# SCH_Project_Final.net
KiCad netlist of a schematic drawn in Altium Designer
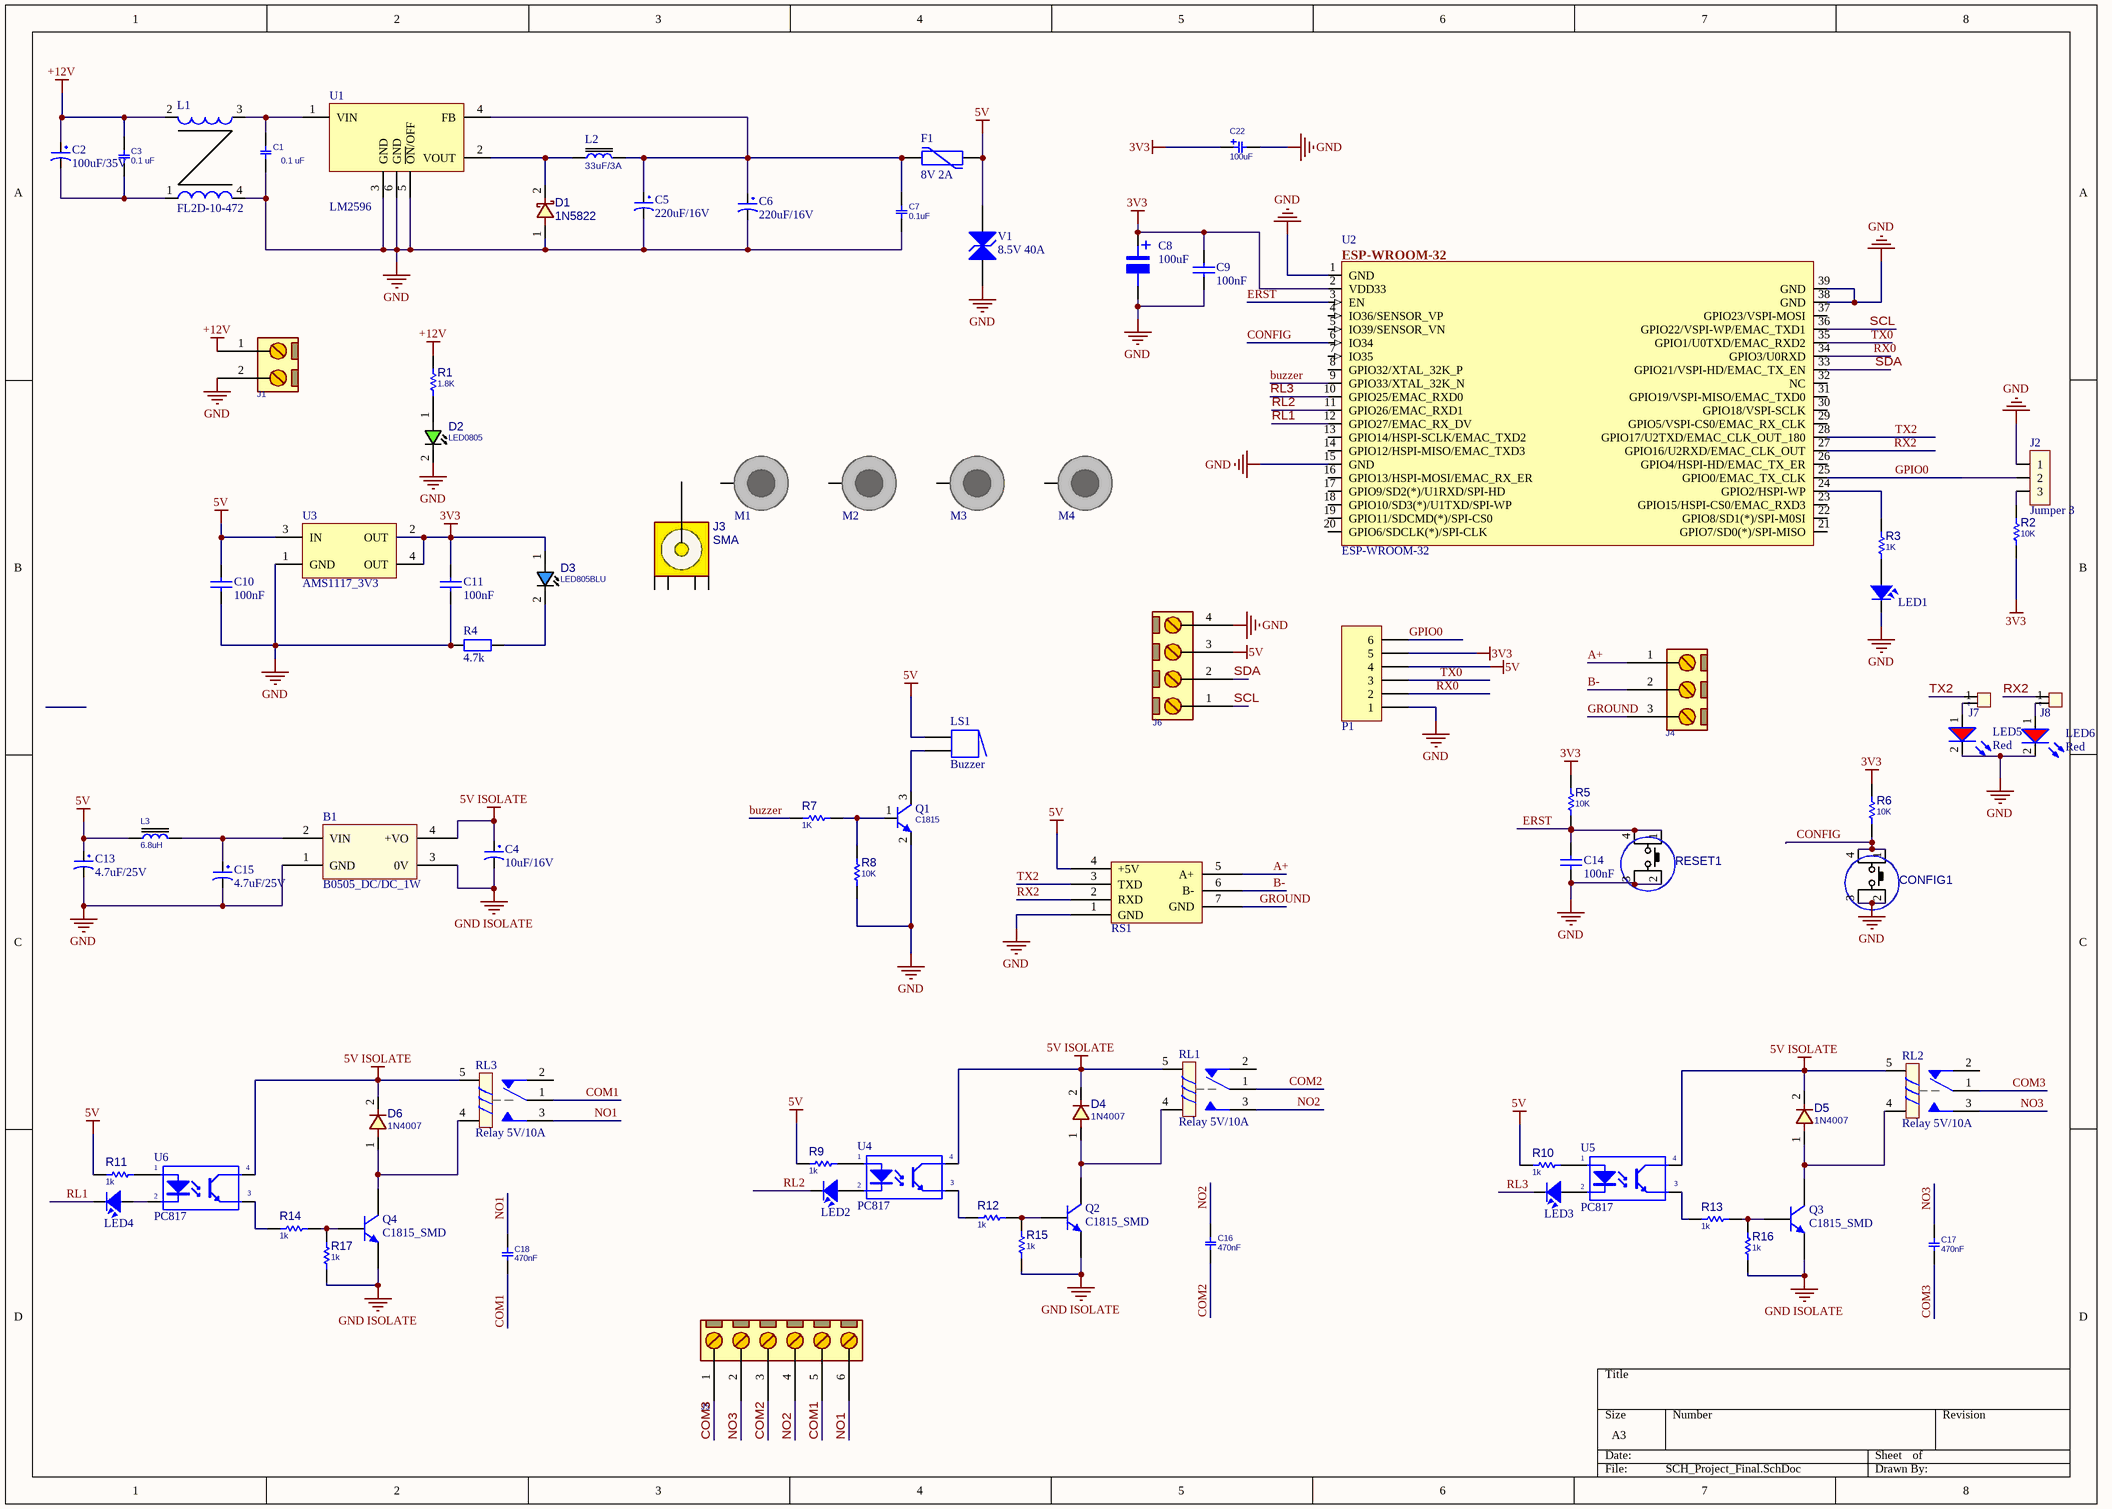
[diagram p0: SCH_Project_Final.SchDoc]

(export (version "E")
  (design (tool "Eeschema 10.0.6"))
  (components
    (comp (ref "B1")
      (value "B0505_DC/DC_1W")
      (footprint "B0505S_DC/DC_1W")
      (libsource (lib "TRANTHANHSANG") (part "B0505_DC/DC_1W"))
    )
    (comp (ref "C1")
      (value "0.1 uF")
      (footprint "cap_0805")
      (description "CAP, MLCC, -F, -V, MATERIAL, -%, 0201")
      (fields (field (name "MANF_P#") "MANF_PART#"))
      (libsource (lib "TRANTHANHSANG") (part "CAP_SMD_0805"))
    )
    (comp (ref "C2")
      (value "100uF/35V")
      (footprint "tu hoa 6.5mm")
      (description "Cắm")
      (libsource (lib "THU VIEN SCH") (part "Tu Hoa 47uF 50V 6x11"))
    )
    (comp (ref "C3")
      (value "0.1 uF")
      (footprint "cap_0805")
      (description "CAP, MLCC, -F, -V, MATERIAL, -%, 0201")
      (fields (field (name "MANF_P#") "MANF_PART#"))
      (libsource (lib "TRANTHANHSANG") (part "CAP_SMD_0805"))
    )
    (comp (ref "C4")
      (value "10uF/16V")
      (footprint "tu hoa 5mm")
      (description "Cắm")
      (libsource (lib "THU VIEN SCH") (part "Tu Hoa 100uF 16V 5x7"))
    )
    (comp (ref "C5")
      (value "220uF/16V")
      (footprint "tu hoa 6.5mm")
      (description "Cắm")
      (libsource (lib "THU VIEN SCH") (part "Tu Hoa 100uF 35V 6x8"))
    )
    (comp (ref "C6")
      (value "220uF/16V")
      (footprint "tu hoa 6.5mm")
      (description "Cắm")
      (libsource (lib "THU VIEN SCH") (part "Tu Hoa 100uF 35V 6x8"))
    )
    (comp (ref "C7")
      (value "0.1uF")
      (footprint "cap_0805")
      (description "CAP, MLCC, -F, -V, MATERIAL, -%, 0201")
      (fields (field (name "MANF_P#") "MANF_PART#"))
      (libsource (lib "TRANTHANHSANG") (part "CAP_SMD_0805"))
    )
    (comp (ref "C8")
      (value "100uF")
      (footprint "tu nhom 6.3 (d)")
      (description "Dán")
      (libsource (lib "THU VIEN SCH") (part "Tu Nhom 100uF 16V"))
    )
    (comp (ref "C9")
      (value "100nF")
      (footprint "cap_0805")
      (description "Dán")
      (libsource (lib "Altium_Lib_by_KhueNguyenCreator") (part "Tu 0805 106 16V 10%"))
    )
    (comp (ref "C10")
      (value "100nF")
      (footprint "cap_0805")
      (description "Dán")
      (libsource (lib "Altium_Lib_by_KhueNguyenCreator") (part "Tu 0805 106 16V 10%"))
    )
    (comp (ref "C11")
      (value "100nF")
      (footprint "cap_0805")
      (description "Dán")
      (libsource (lib "Altium_Lib_by_KhueNguyenCreator") (part "Tu 0805 106 16V 10%"))
    )
    (comp (ref "C13")
      (value "4.7uF/25V")
      (footprint "tu hoa 5mm")
      (description "Cắm")
      (libsource (lib "THU VIEN SCH") (part "Tu Hoa 47uF 35V 5x11"))
    )
    (comp (ref "C14")
      (value "100nF")
      (footprint "cap_0805")
      (description "Dán")
      (libsource (lib "Altium_Lib_by_KhueNguyenCreator") (part "Tu 0805 106 16V 10%"))
    )
    (comp (ref "C15")
      (value "4.7uF/25V")
      (footprint "tu hoa 5mm")
      (description "Cắm")
      (libsource (lib "THU VIEN SCH") (part "Tu Hoa 47uF 35V 5x11"))
    )
    (comp (ref "C16")
      (value "470nF")
      (footprint "C_PLY_19X8")
      (description "CAP, FILM,")
      (fields (field (name "MANF_P#") "MANF_PART#") (field (name "MANF") "MANF"))
      (libsource (lib "AH_Library") (part "CAP_THD_FILM_POLYESTER"))
    )
    (comp (ref "C17")
      (value "470nF")
      (footprint "C_PLY_19X8")
      (description "CAP, FILM,")
      (fields (field (name "MANF_P#") "MANF_PART#") (field (name "MANF") "MANF"))
      (libsource (lib "AH_Library") (part "CAP_THD_FILM_POLYESTER"))
    )
    (comp (ref "C18")
      (value "470nF")
      (footprint "C_PLY_19X8")
      (description "CAP, FILM,")
      (fields (field (name "MANF_P#") "MANF_PART#") (field (name "MANF") "MANF"))
      (libsource (lib "AH_Library") (part "CAP_THD_FILM_POLYESTER"))
    )
    (comp (ref "C22")
      (value "100uF")
      (footprint "C_TN_7343")
      (description "CAP, SMD, TAN,")
      (libsource (lib "AH_Library") (part "CAP_SMD_TAN_7343"))
    )
    (comp (ref "CONFIG1")
      (value "PUSHBUTTON")
      (footprint "SWPBS_SPDT_6X6X5")
      (description "SWITCH, PUSH BUTTON, TACTILE, SMD, SPDT, 6X6X5mm")
      (libsource (lib "AH_Library") (part "SWPBS_SPDT_6X6X5"))
    )
    (comp (ref "D1")
      (value "1N5822")
      (footprint "DIODE_SMD")
      (description "DIODE, SCHOTTKY, 40V, 3A")
      (fields (field (name "MANF") "DIODES"))
      (libsource (lib "TRANTHANHSANG") (part "DIODE_SMD_SCHOTTKY_1N5822"))
    )
    (comp (ref "D2")
      (value "LED0805")
      (footprint "LED0805")
      (description "LED, SMD, 0805")
      (fields (field (name "MANF") "MANF") (field (name "MANF_P#") "MANF_PART#"))
      (libsource (lib "TRANTHANHSANG") (part "LED_SMD_0805"))
    )
    (comp (ref "D3")
      (value "LED805BLU")
      (footprint "LED0805RED")
      (description "LED, SMD, 0805, BLUE")
      (fields (field (name "MANF") "MANF") (field (name "MANF_P#") "MANF_PART#"))
      (libsource (lib "AH_Library") (part "LED_SMD_0805_BLU"))
    )
    (comp (ref "D4")
      (value "1N4007")
      (footprint "D_SMA")
      (description "DIODE, GENERAL PURPOSE, 1000V/1A")
      (fields (field (name "MANF") "Kingtronics") (field (name "MANF_P#") "M7"))
      (libsource (lib "AH_Library") (part "DIODE_SMD_1N4007"))
    )
    (comp (ref "D5")
      (value "1N4007")
      (footprint "D_SMA")
      (description "DIODE, GENERAL PURPOSE, 1000V/1A")
      (fields (field (name "MANF") "Kingtronics") (field (name "MANF_P#") "M7"))
      (libsource (lib "AH_Library") (part "DIODE_SMD_1N4007"))
    )
    (comp (ref "D6")
      (value "1N4007")
      (footprint "D_SMA")
      (description "DIODE, GENERAL PURPOSE, 1000V/1A")
      (fields (field (name "MANF") "Kingtronics") (field (name "MANF_P#") "M7"))
      (libsource (lib "AH_Library") (part "DIODE_SMD_1N4007"))
    )
    (comp (ref "F1")
      (value "8V 2A")
      (footprint "FUSE_RESETTABLE_SMD_1812")
      (description "PTC RESET FUSE 8V 2A 1812")
      (fields (field (name "MANUFACTURER") "Bourns") (field (name "MANUFACTURER PART NUMBER") "MF-MSMF200-2"))
      (libsource (lib "Indruino") (part "FUSE_MF-MSMF200-2"))
    )
    (comp (ref "J1")
      (value "CONN_TB2")
      (footprint "MSTB_2")
      (description "CONN, PHOENIX MSTB, 5-G, 5.08mm pitch")
      (libsource (lib "AH_Library") (part "CONN_MSTB_2"))
    )
    (comp (ref "J2") (value "Jumper 3") (footprint "JP3") (libsource (lib "TRANTHANHSANG") (part "JP3")))
    (comp (ref "J3")
      (value "SMA")
      (footprint "SMA_RA")
      (description "CONN, RF, SMA, Right Angle")
      (fields (field (name "MANF_P#") "SMA-J-P-H-RA-TH1") (field (name "MANF") "Samtec"))
      (libsource (lib "AH_Library") (part "CONN_RF_SMA_RA"))
    )
    (comp (ref "J4")
      (value "CONN_TB3")
      (footprint "MSTB_3")
      (description "CONN, PHOENIX MSTB, 5-G, 5.08mm pitch")
      (libsource (lib "AH_Library") (part "CONN_MSTB_3"))
    )
    (comp (ref "J5")
      (value "CONN_TB6")
      (footprint "MSTB_6")
      (description "CONN, PHOENIX MSTB, 5-G, 5.08mm pitch")
      (libsource (lib "AH_Library") (part "CONN_MSTB_6"))
    )
    (comp (ref "J6")
      (value "CONN_TB4")
      (footprint "MSTB_4")
      (description "CONN, PHOENIX MSTB, 5-G, 5.08mm pitch")
      (libsource (lib "AH_Library") (part "CONN_MSTB_4"))
    )
    (comp (ref "J7") (value "Jumper 2") (footprint "JP2") (libsource (lib "TRANTHANHSANG") (part "JP 2")))
    (comp (ref "J8") (value "Jumper 2") (footprint "JP2") (libsource (lib "TRANTHANHSANG") (part "JP 2")))
    (comp (ref "L1")
      (value "FL2D-10-472")
      (footprint "INDC_FL2D-10-472")
      (description "4.7uH, 1A")
      (libsource (lib "Indruino") (part "IND_FL2D-10-472"))
    )
    (comp (ref "L2")
      (value "33uF/3A")
      (footprint "L_BODY 12X12")
      (description "L_BODY_13.5X12.5")
      (libsource (lib "TRANTHANHSANG") (part "L_BODY_13.5X12.5"))
    )
    (comp (ref "L3")
      (value "6.8uH")
      (footprint "L1008")
      (description "INDUCTOR, 6.8uH, 1.6A, 440mOhm, 1008")
      (fields (field (name "MANF_P#") "VLS252012HBU-6R8M") (field (name "MANF") "TDK"))
      (libsource (lib "AH_Library") (part "IND_SMD_6.8uH_1.6A_1008"))
    )
    (comp (ref "LED1") (value "LED") (footprint "LED0805GRN") (libsource (lib "LIBRARY1") (part "LED SMD")))
    (comp (ref "LED2") (value "LED") (footprint "LED0805BLU") (libsource (lib "LIBRARY1") (part "LED SMD")))
    (comp (ref "LED3") (value "LED") (footprint "LED0805BLU") (libsource (lib "LIBRARY1") (part "LED SMD")))
    (comp (ref "LED4") (value "LED") (footprint "LED0805BLU") (libsource (lib "LIBRARY1") (part "LED SMD")))
    (comp (ref "LED5")
      (value "Red")
      (footprint "LED5R")
      (description "LED Red 3mm/5MM")
      (fields (field (name "Comment") "LED_R_3"))
      (libsource (lib "TRANTHANHSANG") (part "LED_RED_3MM"))
    )
    (comp (ref "LED6")
      (value "Red")
      (footprint "LED5R")
      (description "LED Red 3mm/5MM")
      (fields (field (name "Comment") "LED_R_3"))
      (libsource (lib "TRANTHANHSANG") (part "LED_RED_3MM"))
    )
    (comp (ref "LS1")
      (value "Buzzer")
      (footprint "Buzzer")
      (description "Magnetic Transducer Buzzer")
      (fields (field (name "PUBLISHER") "Altium Limited"))
      (libsource (lib "hphonglib") (part "Buzzer"))
    )
    (comp (ref "M1")
      (value "DNP/MH")
      (footprint "SCMH_M4")
      (description "SCREW mouting, M4, 4mm diameter and 8.0mm PanHead")
      (libsource (lib "AH_Library") (part "SCMH_M4"))
    )
    (comp (ref "M2")
      (value "DNP/MH")
      (footprint "SCMH_M4")
      (description "SCREW mouting, M4, 4mm diameter and 8.0mm PanHead")
      (libsource (lib "AH_Library") (part "SCMH_M4"))
    )
    (comp (ref "M3")
      (value "DNP/MH")
      (footprint "SCMH_M4")
      (description "SCREW mouting, M4, 4mm diameter and 8.0mm PanHead")
      (libsource (lib "AH_Library") (part "SCMH_M4"))
    )
    (comp (ref "M4")
      (value "DNP/MH")
      (footprint "SCMH_M4")
      (description "SCREW mouting, M4, 4mm diameter and 8.0mm PanHead")
      (libsource (lib "AH_Library") (part "SCMH_M4"))
    )
    (comp (ref "P1")
      (value "Header 6")
      (footprint "JP6")
      (description "Header, 6-Pin")
      (fields (field (name "PUBLISHER") "Altium Limited"))
      (libsource (lib "TechMT.VN_Lib_Project") (part "Header 6"))
    )
    (comp (ref "Q1")
      (value "C1815")
      (footprint "SOT23_3")
      (description "BJT, NPN, 50v, 0.15A, SMD, SOT23")
      (libsource (lib "AH_Library") (part "NPN_C1815_SOT23"))
    )
    (comp (ref "Q2")
      (value "C1815_SMD")
      (footprint "trans_smd")
      (description "NPN General Purpose Amplifier")
      (fields (field (name "PUBLISHER") "Altium Limited"))
      (libsource (lib "TRANTHANHSANG") (part "C1815_SMD"))
    )
    (comp (ref "Q3")
      (value "C1815_SMD")
      (footprint "trans_smd")
      (description "NPN General Purpose Amplifier")
      (fields (field (name "PUBLISHER") "Altium Limited"))
      (libsource (lib "TRANTHANHSANG") (part "C1815_SMD"))
    )
    (comp (ref "Q4")
      (value "C1815_SMD")
      (footprint "trans_smd")
      (description "NPN General Purpose Amplifier")
      (fields (field (name "PUBLISHER") "Altium Limited"))
      (libsource (lib "TRANTHANHSANG") (part "C1815_SMD"))
    )
    (comp (ref "R1")
      (value "1.8K")
      (footprint "R0805")
      (description "RESISTOR, SMD, SENS, 0.01Ohm, 0.5W")
      (fields (field (name "MANF_P#") "WSLP0805R0100FEA") (field (name "MANF") "VISHAY"))
      (libsource (lib "TRANTHANHSANG") (part "RES_SMD_0805"))
    )
    (comp (ref "R2")
      (value "10K")
      (footprint "R0805")
      (description "RESISTOR, SMD")
      (libsource (lib "AH_Library") (part "RES_SMD_0805"))
    )
    (comp (ref "R3")
      (value "1K")
      (footprint "R0805")
      (description "RESISTOR, SMD")
      (libsource (lib "AH_Library") (part "RES_SMD_0805"))
    )
    (comp (ref "R4")
      (value "4.7k")
      (footprint "RES-SMD-0805")
      (description "Dán")
      (libsource (lib "Altium_Lib_by_KhueNguyenCreator") (part "Tro 0805 5% 1.8k"))
    )
    (comp (ref "R5")
      (value "10K")
      (footprint "R0805")
      (description "RESISTOR, SMD")
      (libsource (lib "AH_Library") (part "RES_SMD_0805"))
    )
    (comp (ref "R6")
      (value "10K")
      (footprint "R0805")
      (description "RESISTOR, SMD")
      (libsource (lib "AH_Library") (part "RES_SMD_0805"))
    )
    (comp (ref "R7")
      (value "1K")
      (footprint "R0805")
      (description "RESISTOR, SMD")
      (libsource (lib "AH_Library") (part "RES_SMD_0805"))
    )
    (comp (ref "R8")
      (value "10K")
      (footprint "R0805")
      (description "RESISTOR, SMD")
      (libsource (lib "AH_Library") (part "RES_SMD_0805"))
    )
    (comp (ref "R9")
      (value "1k")
      (footprint "R0805")
      (description "RESISTOR, SMD")
      (libsource (lib "AH_Library") (part "RES_SMD_0805"))
    )
    (comp (ref "R10")
      (value "1k")
      (footprint "R0805")
      (description "RESISTOR, SMD")
      (libsource (lib "AH_Library") (part "RES_SMD_0805"))
    )
    (comp (ref "R11")
      (value "1k")
      (footprint "R0805")
      (description "RESISTOR, SMD")
      (libsource (lib "AH_Library") (part "RES_SMD_0805"))
    )
    (comp (ref "R12")
      (value "1k")
      (footprint "R0805")
      (description "RESISTOR, SMD")
      (libsource (lib "AH_Library") (part "RES_SMD_0805"))
    )
    (comp (ref "R13")
      (value "1k")
      (footprint "R0805")
      (description "RESISTOR, SMD")
      (libsource (lib "AH_Library") (part "RES_SMD_0805"))
    )
    (comp (ref "R14")
      (value "1k")
      (footprint "R0805")
      (description "RESISTOR, SMD")
      (libsource (lib "AH_Library") (part "RES_SMD_0805"))
    )
    (comp (ref "R15")
      (value "1k")
      (footprint "R0805")
      (description "RESISTOR, SMD")
      (libsource (lib "AH_Library") (part "RES_SMD_0805"))
    )
    (comp (ref "R16")
      (value "1k")
      (footprint "R0805")
      (description "RESISTOR, SMD")
      (libsource (lib "AH_Library") (part "RES_SMD_0805"))
    )
    (comp (ref "R17")
      (value "1k")
      (footprint "R0805")
      (description "RESISTOR, SMD")
      (libsource (lib "AH_Library") (part "RES_SMD_0805"))
    )
    (comp (ref "RESET1")
      (value "PUSHBUTTON")
      (footprint "SWPBS_SPDT_6X6X5")
      (description "SWITCH, PUSH BUTTON, TACTILE, SMD, SPDT, 6X6X5mm")
      (libsource (lib "AH_Library") (part "SWPBS_SPDT_6X6X5"))
    )
    (comp (ref "RL1")
      (value "Relay 5V/10A")
      (footprint "RL_10A_5V")
      (description "Relay SPDT,10A - 12VDC 5 Pin")
      (libsource (lib "lpson") (part "Relay 5V10A"))
    )
    (comp (ref "RL2")
      (value "Relay 5V/10A")
      (footprint "RL_10A_5V")
      (description "Relay SPDT,10A - 12VDC 5 Pin")
      (libsource (lib "lpson") (part "Relay 5V10A"))
    )
    (comp (ref "RL3")
      (value "Relay 5V/10A")
      (footprint "RL_10A_5V")
      (description "Relay SPDT,10A - 12VDC 5 Pin")
      (libsource (lib "lpson") (part "Relay 5V10A"))
    )
    (comp (ref "RS1")
      (value "RS485_VISION2")
      (footprint "RS485 - Version2")
      (libsource (lib "TRANTHANHSANG") (part "RS485_VISION2"))
    )
    (comp (ref "U1")
      (value "LM2596")
      (footprint "MinhTien_PcbLib:TO263-5")
      (description "1A Regulator")
      (libsource (lib "MinhTien_SCHLib") (part "LM2596"))
    )
    (comp (ref "U2")
      (value "ESP-WROOM-32")
      (footprint "ESP32 WROOM")
      (libsource (lib "lpson") (part "ESP-WROOM-32"))
    )
    (comp (ref "U3")
      (value "AMS1117_3V3")
      (footprint "MinhTien_PcbLib:SOT223-4M")
      (description "1A Regulator")
      (libsource (lib "MinhTien_SCHLib") (part "AMS1117_3V3"))
    )
    (comp (ref "U4")
      (value "PC817")
      (footprint "PhotoCoupler_SMD")
      (description "Single Opto")
      (libsource (lib "lpson") (part "PC817_1"))
    )
    (comp (ref "U5")
      (value "PC817")
      (footprint "PhotoCoupler_SMD")
      (description "Single Opto")
      (libsource (lib "lpson") (part "PC817_1"))
    )
    (comp (ref "U6")
      (value "PC817")
      (footprint "PhotoCoupler_SMD")
      (description "Single Opto")
      (libsource (lib "lpson") (part "PC817_1"))
    )
    (comp (ref "V1")
      (value "8.5V 40A")
      (footprint "INDC0805")
      (description "VARISTOR 8.5V 40A 0805")
      (fields
        (field (name "MANUFACTURER") "Kyocera AVX")
        (field (name "MANUFACTURER PART NUMBER") "VC080505A150RP")
      )
      (libsource (lib "Indruino") (part "VARISTOR_VC080505A150RP"))
    )
  )
  (nets
    (net (code "1") (name "+12V") (class "Default")
      (node (ref "C2") (pin "1") (pinfunction "1_1") (pintype "passive"))
      (node (ref "C3") (pin "2") (pinfunction "2_2") (pintype "passive"))
      (node (ref "J1") (pin "1") (pinfunction "1_1") (pintype "passive"))
      (node (ref "L1") (pin "2") (pinfunction "2_2") (pintype "passive"))
      (node (ref "R1") (pin "2") (pinfunction "2_2") (pintype "passive"))
    )
    (net (code "2") (name "/A+") (class "Default")
      (node (ref "J4") (pin "1") (pinfunction "1_1") (pintype "passive"))
      (node (ref "RS1") (pin "5") (pinfunction "A+_5") (pintype "passive"))
    )
    (net (code "3") (name "/B-") (class "Default")
      (node (ref "J4") (pin "2") (pinfunction "2_2") (pintype "passive"))
      (node (ref "RS1") (pin "6") (pinfunction "B-_6") (pintype "passive"))
    )
    (net (code "4") (name "/COM1") (class "Default")
      (node (ref "C18") (pin "1") (pinfunction "1_1") (pintype "passive"))
      (node (ref "J5") (pin "5") (pinfunction "5_5") (pintype "passive"))
      (node (ref "RL3") (pin "1") (pinfunction "1_1") (pintype "passive"))
    )
    (net (code "5") (name "/COM2") (class "Default")
      (node (ref "C16") (pin "1") (pinfunction "1_1") (pintype "passive"))
      (node (ref "J5") (pin "3") (pinfunction "3_3") (pintype "passive"))
      (node (ref "RL1") (pin "1") (pinfunction "1_1") (pintype "passive"))
    )
    (net (code "6") (name "/COM3") (class "Default")
      (node (ref "C17") (pin "1") (pinfunction "1_1") (pintype "passive"))
      (node (ref "J5") (pin "1") (pinfunction "1_1") (pintype "passive"))
      (node (ref "RL2") (pin "1") (pinfunction "1_1") (pintype "passive"))
    )
    (net (code "7") (name "/CONFIG") (class "Default")
      (node (ref "CONFIG1") (pin "1") (pinfunction "P1_1") (pintype "passive"))
      (node (ref "CONFIG1") (pin "4") (pinfunction "P2_4") (pintype "passive"))
      (node (ref "R6") (pin "2") (pinfunction "2_2") (pintype "passive"))
      (node (ref "U2") (pin "6") (pinfunction "IO34_6") (pintype "input"))
    )
    (net (code "8") (name "/ERST") (class "Default")
      (node (ref "C14") (pin "1") (pinfunction "1_1") (pintype "passive"))
      (node (ref "R5") (pin "2") (pinfunction "2_2") (pintype "passive"))
      (node (ref "RESET1") (pin "1") (pinfunction "P1_1") (pintype "passive"))
      (node (ref "RESET1") (pin "4") (pinfunction "P2_4") (pintype "passive"))
      (node (ref "U2") (pin "3") (pinfunction "EN_3") (pintype "input"))
    )
    (net (code "9") (name "/GPIO0") (class "Default")
      (node (ref "J2") (pin "2") (pinfunction "2_2") (pintype "passive"))
      (node (ref "P1") (pin "6") (pinfunction "6_6") (pintype "passive"))
      (node (ref "U2") (pin "25") (pinfunction "GPIO0/EMAC_TX_CLK_25") (pintype "passive"))
    )
    (net (code "10") (name "/GROUND") (class "Default")
      (node (ref "J4") (pin "3") (pinfunction "3_3") (pintype "passive"))
      (node (ref "RS1") (pin "7") (pinfunction "GND_7") (pintype "passive"))
    )
    (net (code "11") (name "/NO1") (class "Default")
      (node (ref "C18") (pin "2") (pinfunction "2_2") (pintype "passive"))
      (node (ref "J5") (pin "6") (pinfunction "6_6") (pintype "passive"))
      (node (ref "RL3") (pin "3") (pinfunction "3_3") (pintype "passive"))
    )
    (net (code "12") (name "/NO2") (class "Default")
      (node (ref "C16") (pin "2") (pinfunction "2_2") (pintype "passive"))
      (node (ref "J5") (pin "4") (pinfunction "4_4") (pintype "passive"))
      (node (ref "RL1") (pin "3") (pinfunction "3_3") (pintype "passive"))
    )
    (net (code "13") (name "/NO3") (class "Default")
      (node (ref "C17") (pin "2") (pinfunction "2_2") (pintype "passive"))
      (node (ref "J5") (pin "2") (pinfunction "2_2") (pintype "passive"))
      (node (ref "RL2") (pin "3") (pinfunction "3_3") (pintype "passive"))
    )
    (net (code "14") (name "/RL1") (class "Default")
      (node (ref "LED4") (pin "2") (pinfunction "2_2") (pintype "passive"))
      (node (ref "U2") (pin "12") (pinfunction "GPIO27/EMAC_RX_DV_12") (pintype "passive"))
    )
    (net (code "15") (name "/RL2") (class "Default")
      (node (ref "LED2") (pin "2") (pinfunction "2_2") (pintype "passive"))
      (node (ref "U2") (pin "11") (pinfunction "GPIO26/EMAC_RXD1_11") (pintype "passive"))
    )
    (net (code "16") (name "/RL3") (class "Default")
      (node (ref "LED3") (pin "2") (pinfunction "2_2") (pintype "passive"))
      (node (ref "U2") (pin "10") (pinfunction "GPIO25/EMAC_RXD0_10") (pintype "passive"))
    )
    (net (code "17") (name "/RX0") (class "Default")
      (node (ref "P1") (pin "2") (pinfunction "2_2") (pintype "passive"))
      (node (ref "U2") (pin "34") (pinfunction "GPIO3/U0RXD_34") (pintype "passive"))
    )
    (net (code "18") (name "/RX2") (class "Default")
      (node (ref "J8") (pin "2") (pinfunction "2_2") (pintype "passive"))
      (node (ref "RS1") (pin "2") (pinfunction "RXD_2") (pintype "passive"))
      (node (ref "U2") (pin "27") (pinfunction "GPIO16/U2RXD/EMAC_CLK_OUT_27") (pintype "passive"))
    )
    (net (code "19") (name "/SCL") (class "Default")
      (node (ref "J6") (pin "1") (pinfunction "1_1") (pintype "passive"))
      (node (ref "U2") (pin "36") (pinfunction "GPIO22/VSPI-WP/EMAC_TXD1_36") (pintype "passive"))
    )
    (net (code "20") (name "/SDA") (class "Default")
      (node (ref "J6") (pin "2") (pinfunction "2_2") (pintype "passive"))
      (node (ref "U2") (pin "33") (pinfunction "GPIO21/VSPI-HD/EMAC_TX_EN_33") (pintype "passive"))
    )
    (net (code "21") (name "/TX0") (class "Default")
      (node (ref "P1") (pin "3") (pinfunction "3_3") (pintype "passive"))
      (node (ref "U2") (pin "35") (pinfunction "GPIO1/U0TXD/EMAC_RXD2_35") (pintype "passive"))
    )
    (net (code "22") (name "/TX2") (class "Default")
      (node (ref "J7") (pin "2") (pinfunction "2_2") (pintype "passive"))
      (node (ref "RS1") (pin "3") (pinfunction "TXD_3") (pintype "passive"))
      (node (ref "U2") (pin "28") (pinfunction "GPIO17/U2TXD/EMAC_CLK_OUT_180_28") (pintype "passive"))
    )
    (net (code "23") (name "/buzzer") (class "Default")
      (node (ref "R7") (pin "2") (pinfunction "2_2") (pintype "passive"))
      (node (ref "U2") (pin "9") (pinfunction "GPIO33/XTAL_32K_N_9") (pintype "passive"))
    )
    (net (code "24") (name "3V3") (class "Default")
      (node (ref "C11") (pin "1") (pinfunction "1_1") (pintype "passive"))
      (node (ref "C22") (pin "1") (pinfunction "1_1") (pintype "passive"))
      (node (ref "C8") (pin "1") (pinfunction "1_1") (pintype "passive"))
      (node (ref "C9") (pin "1") (pinfunction "1_1") (pintype "passive"))
      (node (ref "D3") (pin "1") (pinfunction "ANODE_1") (pintype "passive"))
      (node (ref "P1") (pin "5") (pinfunction "5_5") (pintype "passive"))
      (node (ref "R2") (pin "2") (pinfunction "2_2") (pintype "passive"))
      (node (ref "R5") (pin "1") (pinfunction "1_1") (pintype "passive"))
      (node (ref "R6") (pin "1") (pinfunction "1_1") (pintype "passive"))
      (node (ref "U2") (pin "2") (pinfunction "VDD33_2") (pintype "passive"))
      (node (ref "U3") (pin "2") (pinfunction "OUT_2") (pintype "passive"))
      (node (ref "U3") (pin "4") (pinfunction "OUT_4") (pintype "passive"))
    )
    (net (code "25") (name "5V") (class "Default")
      (node (ref "C10") (pin "1") (pinfunction "1_1") (pintype "passive"))
      (node (ref "C13") (pin "1") (pinfunction "1_1") (pintype "passive"))
      (node (ref "F1") (pin "2") (pinfunction "2_2") (pintype "passive"))
      (node (ref "J6") (pin "3") (pinfunction "3_3") (pintype "passive"))
      (node (ref "L3") (pin "1") (pinfunction "1_1") (pintype "passive"))
      (node (ref "LS1") (pin "1") (pinfunction "1_1") (pintype "passive"))
      (node (ref "P1") (pin "4") (pinfunction "4_4") (pintype "passive"))
      (node (ref "R10") (pin "2") (pinfunction "2_2") (pintype "passive"))
      (node (ref "R11") (pin "2") (pinfunction "2_2") (pintype "passive"))
      (node (ref "R9") (pin "2") (pinfunction "2_2") (pintype "passive"))
      (node (ref "RS1") (pin "4") (pinfunction "+5V_4") (pintype "passive"))
      (node (ref "U3") (pin "3") (pinfunction "IN_3") (pintype "power_in"))
      (node (ref "V1") (pin "1") (pinfunction "1_1") (pintype "passive"))
    )
    (net (code "26") (name "5V ISOLATE") (class "Default")
      (node (ref "B1") (pin "4") (pinfunction "+VO_4") (pintype "passive"))
      (node (ref "C4") (pin "1") (pinfunction "1_1") (pintype "passive"))
      (node (ref "D4") (pin "2") (pinfunction "2_2") (pintype "passive"))
      (node (ref "D5") (pin "2") (pinfunction "2_2") (pintype "passive"))
      (node (ref "D6") (pin "2") (pinfunction "2_2") (pintype "passive"))
      (node (ref "RL1") (pin "5") (pinfunction "5_5") (pintype "passive"))
      (node (ref "RL2") (pin "5") (pinfunction "5_5") (pintype "passive"))
      (node (ref "RL3") (pin "5") (pinfunction "5_5") (pintype "passive"))
      (node (ref "U4") (pin "4") (pinfunction "C_4") (pintype "passive"))
      (node (ref "U5") (pin "4") (pinfunction "C_4") (pintype "passive"))
      (node (ref "U6") (pin "4") (pinfunction "C_4") (pintype "passive"))
    )
    (net (code "27") (name "GND") (class "Default")
      (node (ref "B1") (pin "1") (pinfunction "GND_1") (pintype "passive"))
      (node (ref "C1") (pin "1") (pinfunction "1_1") (pintype "passive"))
      (node (ref "C10") (pin "2") (pinfunction "2_2") (pintype "passive"))
      (node (ref "C11") (pin "2") (pinfunction "2_2") (pintype "passive"))
      (node (ref "C13") (pin "2") (pinfunction "2_2") (pintype "passive"))
      (node (ref "C14") (pin "2") (pinfunction "2_2") (pintype "passive"))
      (node (ref "C15") (pin "2") (pinfunction "2_2") (pintype "passive"))
      (node (ref "C22") (pin "2") (pinfunction "2_2") (pintype "passive"))
      (node (ref "C5") (pin "2") (pinfunction "2_2") (pintype "passive"))
      (node (ref "C6") (pin "2") (pinfunction "2_2") (pintype "passive"))
      (node (ref "C7") (pin "1") (pinfunction "1_1") (pintype "passive"))
      (node (ref "C8") (pin "2") (pinfunction "2_2") (pintype "passive"))
      (node (ref "C9") (pin "2") (pinfunction "2_2") (pintype "passive"))
      (node (ref "CONFIG1") (pin "2") (pinfunction "P3_2") (pintype "passive"))
      (node (ref "CONFIG1") (pin "3") (pinfunction "P4_3") (pintype "passive"))
      (node (ref "D1") (pin "1") (pinfunction "1_1") (pintype "passive"))
      (node (ref "D2") (pin "2") (pinfunction "CATHODE_2") (pintype "passive"))
      (node (ref "J1") (pin "2") (pinfunction "2_2") (pintype "passive"))
      (node (ref "J2") (pin "1") (pinfunction "1_1") (pintype "passive"))
      (node (ref "J6") (pin "4") (pinfunction "4_4") (pintype "passive"))
      (node (ref "L1") (pin "4") (pinfunction "4_4") (pintype "passive"))
      (node (ref "LED1") (pin "2") (pinfunction "2_2") (pintype "passive"))
      (node (ref "LED5") (pin "2") (pinfunction "K_2") (pintype "passive"))
      (node (ref "LED6") (pin "2") (pinfunction "K_2") (pintype "passive"))
      (node (ref "P1") (pin "1") (pinfunction "1_1") (pintype "passive"))
      (node (ref "Q1") (pin "2") (pinfunction "E_2") (pintype "passive"))
      (node (ref "R4") (pin "2") (pinfunction "2_2") (pintype "passive"))
      (node (ref "R8") (pin "2") (pinfunction "2_2") (pintype "passive"))
      (node (ref "RESET1") (pin "2") (pinfunction "P3_2") (pintype "passive"))
      (node (ref "RESET1") (pin "3") (pinfunction "P4_3") (pintype "passive"))
      (node (ref "RS1") (pin "1") (pinfunction "GND_1") (pintype "passive"))
      (node (ref "U1") (pin "3") (pinfunction "GND_3") (pintype "passive"))
      (node (ref "U1") (pin "5") (pinfunction "~{ON}/OFF_5") (pintype "passive"))
      (node (ref "U1") (pin "6") (pinfunction "GND_6") (pintype "passive"))
      (node (ref "U2") (pin "1") (pinfunction "GND_1") (pintype "passive"))
      (node (ref "U2") (pin "15") (pinfunction "GND_15") (pintype "passive"))
      (node (ref "U2") (pin "38") (pinfunction "GND_38") (pintype "passive"))
      (node (ref "U2") (pin "39") (pinfunction "GND_39") (pintype "passive"))
      (node (ref "U3") (pin "1") (pinfunction "GND_1") (pintype "power_in"))
      (node (ref "V1") (pin "2") (pinfunction "2_2") (pintype "passive"))
    )
    (net (code "28") (name "GND ISOLATE") (class "Default")
      (node (ref "B1") (pin "3") (pinfunction "0V_3") (pintype "passive"))
      (node (ref "C4") (pin "2") (pinfunction "2_2") (pintype "passive"))
      (node (ref "Q2") (pin "2") (pinfunction "E_2") (pintype "passive"))
      (node (ref "Q3") (pin "2") (pinfunction "E_2") (pintype "passive"))
      (node (ref "Q4") (pin "2") (pinfunction "E_2") (pintype "passive"))
      (node (ref "R15") (pin "1") (pinfunction "1_1") (pintype "passive"))
      (node (ref "R16") (pin "1") (pinfunction "1_1") (pintype "passive"))
      (node (ref "R17") (pin "1") (pinfunction "1_1") (pintype "passive"))
    )
    (net (code "29") (name "Net-(B1-VIN)") (class "Default")
      (node (ref "B1") (pin "2") (pinfunction "VIN_2") (pintype "passive"))
      (node (ref "C15") (pin "1") (pinfunction "1_1") (pintype "passive"))
      (node (ref "L3") (pin "2") (pinfunction "2_2") (pintype "passive"))
    )
    (net (code "30") (name "Net-(C2-Pad2)") (class "Default")
      (node (ref "C2") (pin "2") (pinfunction "2_2") (pintype "passive"))
      (node (ref "C3") (pin "1") (pinfunction "1_1") (pintype "passive"))
      (node (ref "L1") (pin "1") (pinfunction "1_1") (pintype "passive"))
    )
    (net (code "31") (name "Net-(D2-ANODE)") (class "Default")
      (node (ref "D2") (pin "1") (pinfunction "ANODE_1") (pintype "passive"))
      (node (ref "R1") (pin "1") (pinfunction "1_1") (pintype "passive"))
    )
    (net (code "32") (name "Net-(D3-CATHODE)") (class "Default")
      (node (ref "D3") (pin "2") (pinfunction "CATHODE_2") (pintype "passive"))
      (node (ref "R4") (pin "1") (pinfunction "1_1") (pintype "passive"))
    )
    (net (code "33") (name "Net-(J2-Pad3)") (class "Default")
      (node (ref "J2") (pin "3") (pinfunction "3_3") (pintype "passive"))
      (node (ref "R2") (pin "1") (pinfunction "1_1") (pintype "passive"))
    )
    (net (code "34") (name "Net-(LED1-Pad1)") (class "Default")
      (node (ref "LED1") (pin "1") (pinfunction "1_1") (pintype "passive"))
      (node (ref "R3") (pin "1") (pinfunction "1_1") (pintype "passive"))
    )
    (net (code "35") (name "Net-(LED5-A)") (class "Default")
      (node (ref "J7") (pin "1") (pinfunction "1_1") (pintype "passive"))
      (node (ref "LED5") (pin "1") (pinfunction "A_1") (pintype "passive"))
    )
    (net (code "36") (name "Net-(LED6-A)") (class "Default")
      (node (ref "J8") (pin "1") (pinfunction "1_1") (pintype "passive"))
      (node (ref "LED6") (pin "1") (pinfunction "A_1") (pintype "passive"))
    )
    (net (code "37") (name "Net-(Q1-B)") (class "Default")
      (node (ref "Q1") (pin "1") (pinfunction "B_1") (pintype "passive"))
      (node (ref "R7") (pin "1") (pinfunction "1_1") (pintype "passive"))
      (node (ref "R8") (pin "1") (pinfunction "1_1") (pintype "passive"))
    )
    (net (code "38") (name "Net-(Q1-C)") (class "Default")
      (node (ref "LS1") (pin "2") (pinfunction "2_2") (pintype "passive"))
      (node (ref "Q1") (pin "3") (pinfunction "C_3") (pintype "passive"))
    )
    (net (code "39") (name "Net-(Q2-B)") (class "Default")
      (node (ref "Q2") (pin "1") (pinfunction "B_1") (pintype "passive"))
      (node (ref "R12") (pin "1") (pinfunction "1_1") (pintype "passive"))
      (node (ref "R15") (pin "2") (pinfunction "2_2") (pintype "passive"))
    )
    (net (code "40") (name "Net-(Q2-C)") (class "Default")
      (node (ref "D4") (pin "1") (pinfunction "1_1") (pintype "passive"))
      (node (ref "Q2") (pin "3") (pinfunction "C_3") (pintype "passive"))
      (node (ref "RL1") (pin "4") (pinfunction "4_4") (pintype "passive"))
    )
    (net (code "41") (name "Net-(Q3-B)") (class "Default")
      (node (ref "Q3") (pin "1") (pinfunction "B_1") (pintype "passive"))
      (node (ref "R13") (pin "1") (pinfunction "1_1") (pintype "passive"))
      (node (ref "R16") (pin "2") (pinfunction "2_2") (pintype "passive"))
    )
    (net (code "42") (name "Net-(Q3-C)") (class "Default")
      (node (ref "D5") (pin "1") (pinfunction "1_1") (pintype "passive"))
      (node (ref "Q3") (pin "3") (pinfunction "C_3") (pintype "passive"))
      (node (ref "RL2") (pin "4") (pinfunction "4_4") (pintype "passive"))
    )
    (net (code "43") (name "Net-(Q4-B)") (class "Default")
      (node (ref "Q4") (pin "1") (pinfunction "B_1") (pintype "passive"))
      (node (ref "R14") (pin "1") (pinfunction "1_1") (pintype "passive"))
      (node (ref "R17") (pin "2") (pinfunction "2_2") (pintype "passive"))
    )
    (net (code "44") (name "Net-(Q4-C)") (class "Default")
      (node (ref "D6") (pin "1") (pinfunction "1_1") (pintype "passive"))
      (node (ref "Q4") (pin "3") (pinfunction "C_3") (pintype "passive"))
      (node (ref "RL3") (pin "4") (pinfunction "4_4") (pintype "passive"))
    )
    (net (code "45") (name "Net-(U1-FB)") (class "Default")
      (node (ref "C5") (pin "1") (pinfunction "1_1") (pintype "passive"))
      (node (ref "C6") (pin "1") (pinfunction "1_1") (pintype "passive"))
      (node (ref "C7") (pin "2") (pinfunction "2_2") (pintype "passive"))
      (node (ref "F1") (pin "1") (pinfunction "1_1") (pintype "passive"))
      (node (ref "L2") (pin "2") (pinfunction "2_2") (pintype "passive"))
      (node (ref "U1") (pin "4") (pinfunction "FB_4") (pintype "passive"))
    )
    (net (code "46") (name "Net-(U1-VIN)") (class "Default")
      (node (ref "C1") (pin "2") (pinfunction "2_2") (pintype "passive"))
      (node (ref "L1") (pin "3") (pinfunction "3_3") (pintype "passive"))
      (node (ref "U1") (pin "1") (pinfunction "VIN_1") (pintype "passive"))
    )
    (net (code "47") (name "Net-(U1-VOUT)") (class "Default")
      (node (ref "D1") (pin "2") (pinfunction "2_2") (pintype "passive"))
      (node (ref "L2") (pin "1") (pinfunction "1_1") (pintype "passive"))
      (node (ref "U1") (pin "2") (pinfunction "VOUT_2") (pintype "passive"))
    )
    (net (code "48") (name "Net-(U2-GPIO2{slash}HSPI-WP)") (class "Default")
      (node (ref "R3") (pin "2") (pinfunction "2_2") (pintype "passive"))
      (node (ref "U2") (pin "24") (pinfunction "GPIO2/HSPI-WP_24") (pintype "passive"))
    )
    (net (code "49") (name "Net-(U4-A)") (class "Default")
      (node (ref "R9") (pin "1") (pinfunction "1_1") (pintype "passive"))
      (node (ref "U4") (pin "1") (pinfunction "A_1") (pintype "passive"))
    )
    (net (code "50") (name "Net-(U4-E)") (class "Default")
      (node (ref "R12") (pin "2") (pinfunction "2_2") (pintype "passive"))
      (node (ref "U4") (pin "3") (pinfunction "E_3") (pintype "passive"))
    )
    (net (code "51") (name "Net-(U4-K)") (class "Default")
      (node (ref "LED2") (pin "1") (pinfunction "1_1") (pintype "passive"))
      (node (ref "U4") (pin "2") (pinfunction "K_2") (pintype "passive"))
    )
    (net (code "52") (name "Net-(U5-A)") (class "Default")
      (node (ref "R10") (pin "1") (pinfunction "1_1") (pintype "passive"))
      (node (ref "U5") (pin "1") (pinfunction "A_1") (pintype "passive"))
    )
    (net (code "53") (name "Net-(U5-E)") (class "Default")
      (node (ref "R13") (pin "2") (pinfunction "2_2") (pintype "passive"))
      (node (ref "U5") (pin "3") (pinfunction "E_3") (pintype "passive"))
    )
    (net (code "54") (name "Net-(U5-K)") (class "Default")
      (node (ref "LED3") (pin "1") (pinfunction "1_1") (pintype "passive"))
      (node (ref "U5") (pin "2") (pinfunction "K_2") (pintype "passive"))
    )
    (net (code "55") (name "Net-(U6-A)") (class "Default")
      (node (ref "R11") (pin "1") (pinfunction "1_1") (pintype "passive"))
      (node (ref "U6") (pin "1") (pinfunction "A_1") (pintype "passive"))
    )
    (net (code "56") (name "Net-(U6-E)") (class "Default")
      (node (ref "R14") (pin "2") (pinfunction "2_2") (pintype "passive"))
      (node (ref "U6") (pin "3") (pinfunction "E_3") (pintype "passive"))
    )
    (net (code "57") (name "Net-(U6-K)") (class "Default")
      (node (ref "LED4") (pin "1") (pinfunction "1_1") (pintype "passive"))
      (node (ref "U6") (pin "2") (pinfunction "K_2") (pintype "passive"))
    )
    (net (code "58") (name "unconnected-(J3-G1-Pad2)") (class "Default")
      (node (ref "J3") (pin "2") (pinfunction "G1_2") (pintype "passive"))
    )
    (net (code "59") (name "unconnected-(J3-G2-Pad3)") (class "Default")
      (node (ref "J3") (pin "3") (pinfunction "G2_3") (pintype "passive"))
    )
    (net (code "60") (name "unconnected-(J3-G3-Pad4)") (class "Default")
      (node (ref "J3") (pin "4") (pinfunction "G3_4") (pintype "passive"))
    )
    (net (code "61") (name "unconnected-(J3-G4-Pad5)") (class "Default")
      (node (ref "J3") (pin "5") (pinfunction "G4_5") (pintype "passive"))
    )
    (net (code "62") (name "unconnected-(J3-SIG-Pad1)") (class "Default")
      (node (ref "J3") (pin "1") (pinfunction "SIG_1") (pintype "passive"))
    )
    (net (code "63") (name "unconnected-(M1-Pad1)") (class "Default")
      (node (ref "M1") (pin "1") (pinfunction "1_1") (pintype "passive"))
    )
    (net (code "64") (name "unconnected-(M2-Pad1)") (class "Default")
      (node (ref "M2") (pin "1") (pinfunction "1_1") (pintype "passive"))
    )
    (net (code "65") (name "unconnected-(M3-Pad1)") (class "Default")
      (node (ref "M3") (pin "1") (pinfunction "1_1") (pintype "passive"))
    )
    (net (code "66") (name "unconnected-(M4-Pad1)") (class "Default")
      (node (ref "M4") (pin "1") (pinfunction "1_1") (pintype "passive"))
    )
    (net (code "67") (name "unconnected-(RL1-Pad2)") (class "Default")
      (node (ref "RL1") (pin "2") (pinfunction "2_2") (pintype "passive"))
    )
    (net (code "68") (name "unconnected-(RL2-Pad2)") (class "Default")
      (node (ref "RL2") (pin "2") (pinfunction "2_2") (pintype "passive"))
    )
    (net (code "69") (name "unconnected-(RL3-Pad2)") (class "Default")
      (node (ref "RL3") (pin "2") (pinfunction "2_2") (pintype "passive"))
    )
    (net (code "70") (name "unconnected-(U2-GPIO4{slash}HSPI-HD{slash}EMAC_TX_ER-Pad26)") (class "Default")
      (node (ref "U2") (pin "26") (pinfunction "GPIO4/HSPI-HD/EMAC_TX_ER_26") (pintype "passive"))
    )
    (net (code "71") (name "unconnected-(U2-GPIO5{slash}VSPI-CS0{slash}EMAC_RX_CLK-Pad29)") (class "Default")
      (node (ref "U2") (pin "29") (pinfunction "GPIO5/VSPI-CS0/EMAC_RX_CLK_29") (pintype "passive"))
    )
    (net (code "72") (name "unconnected-(U2-GPIO6{slash}SDCLK(*){slash}SPI-CLK-Pad20)") (class "Default")
      (node (ref "U2") (pin "20") (pinfunction "GPIO6/SDCLK(*)/SPI-CLK_20") (pintype "passive"))
    )
    (net (code "73") (name "unconnected-(U2-GPIO7{slash}SD0(*){slash}SPI-MISO-Pad21)") (class "Default")
      (node (ref "U2") (pin "21") (pinfunction "GPIO7/SD0(*)/SPI-MISO_21") (pintype "passive"))
    )
    (net (code "74") (name "unconnected-(U2-GPIO8{slash}SD1(*){slash}SPI-M0SI-Pad22)") (class "Default")
      (node (ref "U2") (pin "22") (pinfunction "GPIO8/SD1(*)/SPI-M0SI_22") (pintype "passive"))
    )
    (net (code "75") (name "unconnected-(U2-GPIO9{slash}SD2(*){slash}U1RXD{slash}SPI-HD-Pad17)") (class "Default")
      (node (ref "U2") (pin "17") (pinfunction "GPIO9/SD2(*)/U1RXD/SPI-HD_17") (pintype "passive"))
    )
    (net (code "76") (name "unconnected-(U2-GPIO10{slash}SD3(*){slash}U1TXD{slash}SPI-WP-Pad18)") (class "Default")
      (node (ref "U2") (pin "18") (pinfunction "GPIO10/SD3(*)/U1TXD/SPI-WP_18") (pintype "passive"))
    )
    (net (code "77") (name "unconnected-(U2-GPIO11{slash}SDCMD(*){slash}SPI-CS0-Pad19)") (class "Default")
      (node (ref "U2") (pin "19") (pinfunction "GPIO11/SDCMD(*)/SPI-CS0_19") (pintype "passive"))
    )
    (net (code "78") (name "unconnected-(U2-GPIO12{slash}HSPI-MISO{slash}EMAC_TXD3-Pad14)") (class "Default")
      (node (ref "U2") (pin "14") (pinfunction "GPIO12/HSPI-MISO/EMAC_TXD3_14") (pintype "passive"))
    )
    (net (code "79") (name "unconnected-(U2-GPIO13{slash}HSPI-MOSI{slash}EMAC_RX_ER-Pad16)") (class "Default")
      (node (ref "U2") (pin "16") (pinfunction "GPIO13/HSPI-MOSI/EMAC_RX_ER_16") (pintype "passive"))
    )
    (net (code "80") (name "unconnected-(U2-GPIO14{slash}HSPI-SCLK{slash}EMAC_TXD2-Pad13)") (class "Default")
      (node (ref "U2") (pin "13") (pinfunction "GPIO14/HSPI-SCLK/EMAC_TXD2_13") (pintype "passive"))
    )
    (net (code "81") (name "unconnected-(U2-GPIO15{slash}HSPI-CS0{slash}EMAC_RXD3-Pad23)") (class "Default")
      (node (ref "U2") (pin "23") (pinfunction "GPIO15/HSPI-CS0/EMAC_RXD3_23") (pintype "passive"))
    )
    (net (code "82") (name "unconnected-(U2-GPIO18{slash}VSPI-SCLK-Pad30)") (class "Default")
      (node (ref "U2") (pin "30") (pinfunction "GPIO18/VSPI-SCLK_30") (pintype "passive"))
    )
    (net (code "83") (name "unconnected-(U2-GPIO19{slash}VSPI-MISO{slash}EMAC_TXD0-Pad31)") (class "Default")
      (node (ref "U2") (pin "31") (pinfunction "GPIO19/VSPI-MISO/EMAC_TXD0_31") (pintype "passive"))
    )
    (net (code "84") (name "unconnected-(U2-GPIO23{slash}VSPI-MOSI-Pad37)") (class "Default")
      (node (ref "U2") (pin "37") (pinfunction "GPIO23/VSPI-MOSI_37") (pintype "passive"))
    )
    (net (code "85") (name "unconnected-(U2-GPIO32{slash}XTAL_32K_P-Pad8)") (class "Default")
      (node (ref "U2") (pin "8") (pinfunction "GPIO32/XTAL_32K_P_8") (pintype "passive"))
    )
    (net (code "86") (name "unconnected-(U2-IO35-Pad7)") (class "Default")
      (node (ref "U2") (pin "7") (pinfunction "IO35_7") (pintype "input"))
    )
    (net (code "87") (name "unconnected-(U2-IO36{slash}SENSOR_VP-Pad4)") (class "Default")
      (node (ref "U2") (pin "4") (pinfunction "IO36/SENSOR_VP_4") (pintype "input"))
    )
    (net (code "88") (name "unconnected-(U2-IO39{slash}SENSOR_VN-Pad5)") (class "Default")
      (node (ref "U2") (pin "5") (pinfunction "IO39/SENSOR_VN_5") (pintype "input"))
    )
    (net (code "89") (name "unconnected-(U2-NC-Pad32)") (class "Default")
      (node (ref "U2") (pin "32") (pinfunction "NC_32") (pintype "passive"))
    )
  )
)
